# M_dulo_U_V_A_v_1_0.net
KiCad netlist of a schematic drawn in EAGLE
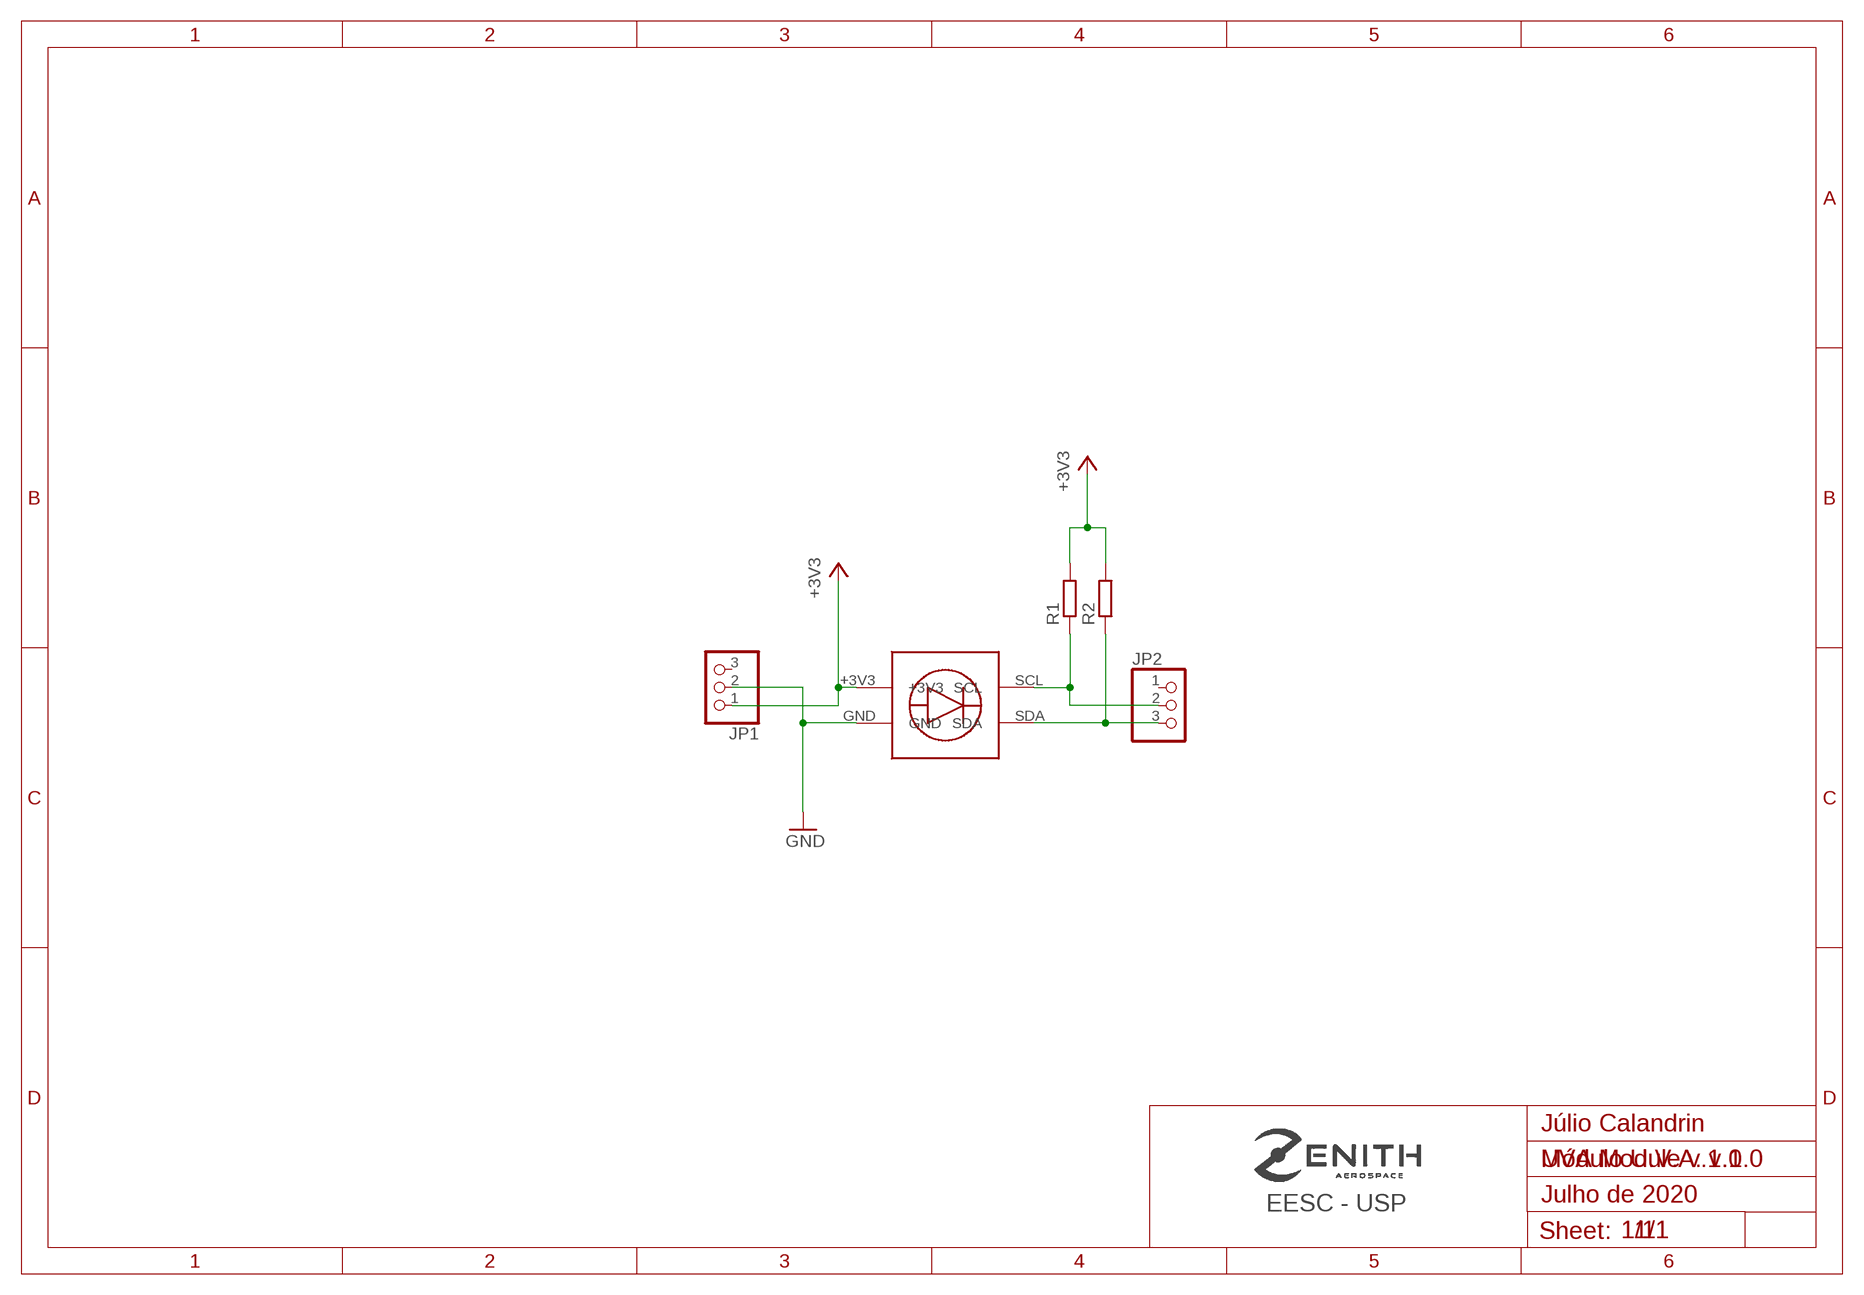
[diagram p0: schematic, sheet 1]

(export (version "E")
  (design (tool "Eeschema 10.0.6"))
  (components
    (comp (ref "JP1")
      (value "PINHD-1X3")
      (footprint "eagle-import:1X03")
      (libsource (lib "eagle-import") (part "PINHD-1X3"))
    )
    (comp (ref "JP2")
      (value "PINHD-1X3")
      (footprint "eagle-import:1X03")
      (libsource (lib "eagle-import") (part "PINHD-1X3"))
    )
    (comp (ref "R1")
      (value "R-EU_R0805")
      (footprint "eagle-import:R0805")
      (libsource (lib "eagle-import") (part "R-EU_R0805"))
    )
    (comp (ref "R2")
      (value "R-EU_R0805")
      (footprint "eagle-import:R0805")
      (libsource (lib "eagle-import") (part "R-EU_R0805"))
    )
    (comp (ref "U$1")
      (value "BREAKOUT_UV-A")
      (footprint "eagle-import:PADS_UV-A_B")
      (libsource (lib "eagle-import") (part "BREAKOUT_UV-A"))
    )
  )
  (nets
    (net (code "1") (name "+3V3") (class "Default")
      (node (ref "JP1") (pin "1") (pinfunction "1_1") (pintype "passive"))
      (node (ref "R1") (pin "2") (pinfunction "2_2") (pintype "passive"))
      (node (ref "R2") (pin "2") (pinfunction "2_2") (pintype "passive"))
      (node (ref "U$1") (pin "+3V3") (pinfunction "+3V3_+3V3") (pintype "bidirectional"))
    )
    (net (code "2") (name "GND") (class "Default")
      (node (ref "JP1") (pin "2") (pinfunction "2_2") (pintype "passive"))
      (node (ref "U$1") (pin "GND") (pinfunction "GND_GND") (pintype "bidirectional"))
    )
    (net (code "3") (name "Net-(JP2-Pad2)") (class "Default")
      (node (ref "JP2") (pin "2") (pinfunction "2_2") (pintype "passive"))
      (node (ref "R1") (pin "1") (pinfunction "1_1") (pintype "passive"))
      (node (ref "U$1") (pin "SCL") (pinfunction "SCL_SCL") (pintype "bidirectional"))
    )
    (net (code "4") (name "Net-(JP2-Pad3)") (class "Default")
      (node (ref "JP2") (pin "3") (pinfunction "3_3") (pintype "passive"))
      (node (ref "R2") (pin "1") (pinfunction "1_1") (pintype "passive"))
      (node (ref "U$1") (pin "SDA") (pinfunction "SDA_SDA") (pintype "bidirectional"))
    )
    (net (code "5") (name "unconnected-(JP1-Pad3)") (class "Default")
      (node (ref "JP1") (pin "3") (pinfunction "3_3") (pintype "passive"))
    )
    (net (code "6") (name "unconnected-(JP2-Pad1)") (class "Default")
      (node (ref "JP2") (pin "1") (pinfunction "1_1") (pintype "passive"))
    )
  )
)
